# Microcontroller.net
KiCad netlist of a schematic drawn in Altium Designer
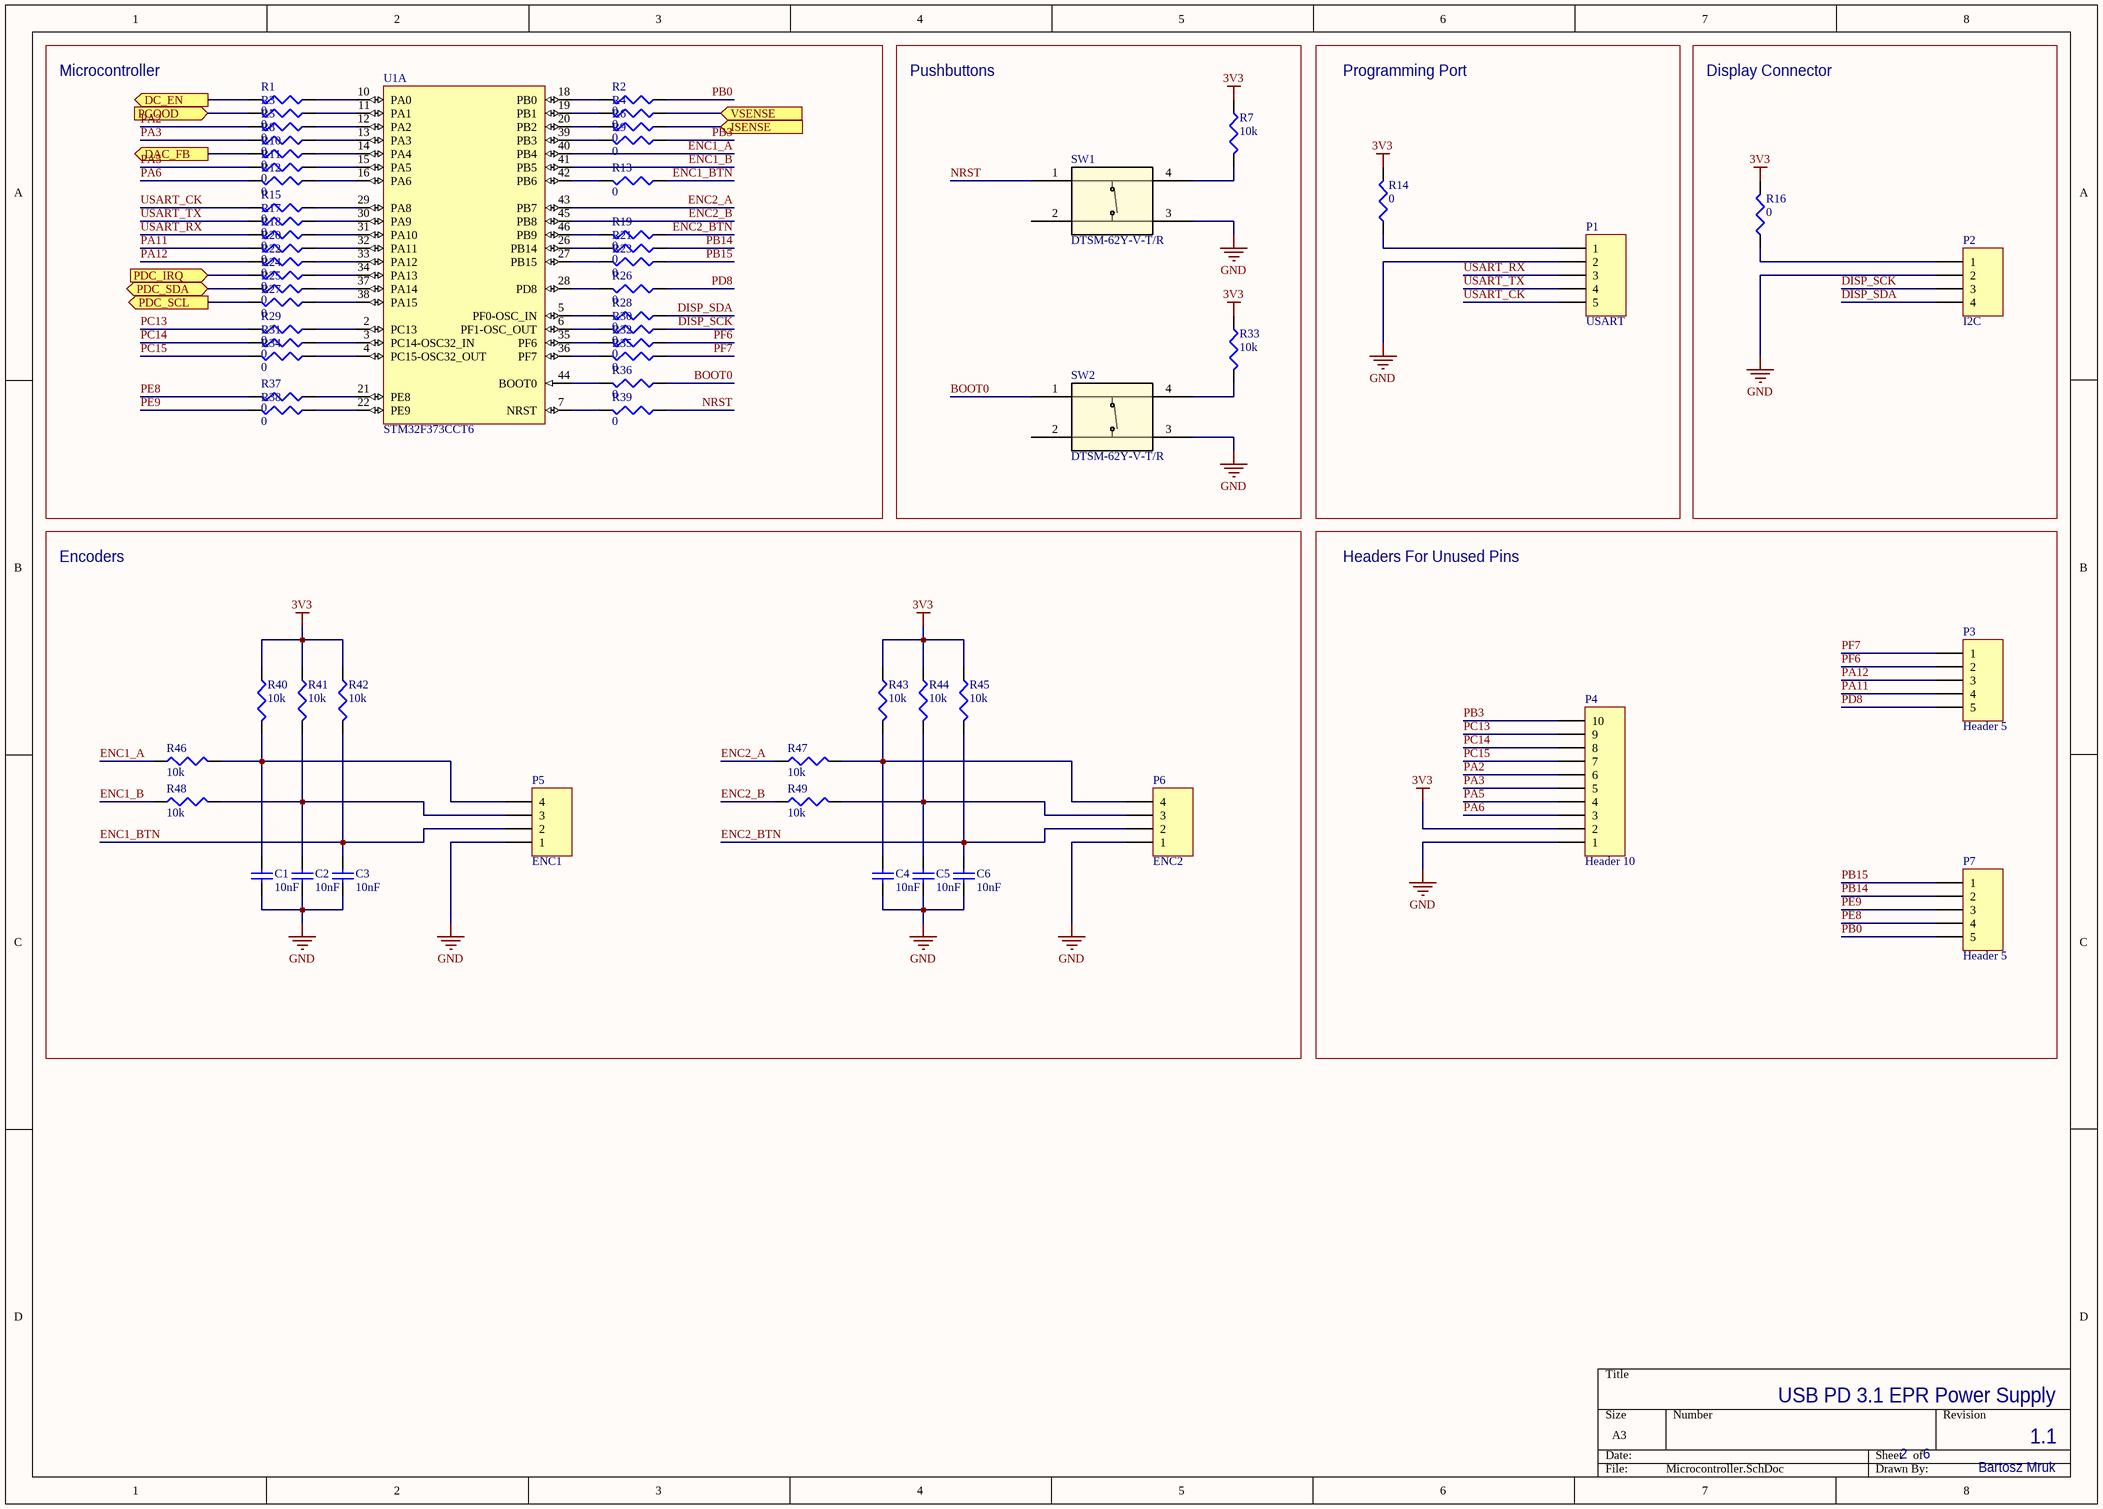
[diagram p0: Microcontroller.SchDoc]

(export (version "E")
  (design (tool "Eeschema 10.0.6"))
  (components
    (comp (ref "C1")
      (value "10nF")
      (footprint "1608[0603]")
      (description "Capacitor (Semiconductor SIM Model)")
      (fields (field (name "Comment") "Cap Semi") (field (name "PUBLISHER") "Altium Limited"))
      (libsource (lib "Miscellaneous Devices") (part "Cap Semi"))
    )
    (comp (ref "C2")
      (value "10nF")
      (footprint "1608[0603]")
      (description "Capacitor (Semiconductor SIM Model)")
      (fields (field (name "Comment") "Cap Semi") (field (name "PUBLISHER") "Altium Limited"))
      (libsource (lib "Miscellaneous Devices") (part "Cap Semi"))
    )
    (comp (ref "C3")
      (value "10nF")
      (footprint "1608[0603]")
      (description "Capacitor (Semiconductor SIM Model)")
      (fields (field (name "Comment") "Cap Semi") (field (name "PUBLISHER") "Altium Limited"))
      (libsource (lib "Miscellaneous Devices") (part "Cap Semi"))
    )
    (comp (ref "C4")
      (value "10nF")
      (footprint "1608[0603]")
      (description "Capacitor (Semiconductor SIM Model)")
      (fields (field (name "Comment") "Cap Semi") (field (name "PUBLISHER") "Altium Limited"))
      (libsource (lib "Miscellaneous Devices") (part "Cap Semi"))
    )
    (comp (ref "C5")
      (value "10nF")
      (footprint "1608[0603]")
      (description "Capacitor (Semiconductor SIM Model)")
      (fields (field (name "Comment") "Cap Semi") (field (name "PUBLISHER") "Altium Limited"))
      (libsource (lib "Miscellaneous Devices") (part "Cap Semi"))
    )
    (comp (ref "C6")
      (value "10nF")
      (footprint "1608[0603]")
      (description "Capacitor (Semiconductor SIM Model)")
      (fields (field (name "Comment") "Cap Semi") (field (name "PUBLISHER") "Altium Limited"))
      (libsource (lib "Miscellaneous Devices") (part "Cap Semi"))
    )
    (comp (ref "P1")
      (value "USART")
      (footprint "HDR1X5")
      (description "Header, 5-Pin")
      (fields (field (name "PUBLISHER") "Altium Limited"))
      (libsource (lib "Miscellaneous Connectors") (part "Header 5"))
    )
    (comp (ref "P2")
      (value "I2C")
      (footprint "HDR1X4")
      (description "Header, 4-Pin")
      (fields (field (name "PUBLISHER") "Altium Limited"))
      (libsource (lib "") (part "Header 4_1"))
    )
    (comp (ref "P3")
      (value "Header 5")
      (footprint "HDR1X5")
      (description "Header, 5-Pin")
      (fields (field (name "PUBLISHER") "Altium Limited"))
      (libsource (lib "Miscellaneous Connectors") (part "Header 5"))
    )
    (comp (ref "P4")
      (value "Header 10")
      (footprint "HDR1X10")
      (description "Header, 10-Pin")
      (fields (field (name "PUBLISHER") "Altium Limited"))
      (libsource (lib "Miscellaneous Connectors") (part "Header 10"))
    )
    (comp (ref "P5")
      (value "ENC1")
      (footprint "HDR1X4")
      (description "Header, 4-Pin")
      (fields (field (name "PUBLISHER") "Altium Limited"))
      (libsource (lib "Miscellaneous Connectors") (part "Header 4"))
    )
    (comp (ref "P6")
      (value "ENC2")
      (footprint "HDR1X4")
      (description "Header, 4-Pin")
      (fields (field (name "PUBLISHER") "Altium Limited"))
      (libsource (lib "Miscellaneous Connectors") (part "Header 4"))
    )
    (comp (ref "P7")
      (value "Header 5")
      (footprint "HDR1X5")
      (description "Header, 5-Pin")
      (fields (field (name "PUBLISHER") "Altium Limited"))
      (libsource (lib "Miscellaneous Connectors") (part "Header 5"))
    )
    (comp (ref "R1")
      (value "0")
      (footprint "J1-0603")
      (description "Resistor")
      (fields (field (name "PUBLISHER") "Altium Limited"))
      (libsource (lib "Miscellaneous Devices") (part "Res3"))
    )
    (comp (ref "R2")
      (value "0")
      (footprint "J1-0603")
      (description "Resistor")
      (fields (field (name "PUBLISHER") "Altium Limited"))
      (libsource (lib "Miscellaneous Devices") (part "Res3"))
    )
    (comp (ref "R3")
      (value "0")
      (footprint "J1-0603")
      (description "Resistor")
      (fields (field (name "PUBLISHER") "Altium Limited"))
      (libsource (lib "Miscellaneous Devices") (part "Res3"))
    )
    (comp (ref "R4")
      (value "0")
      (footprint "J1-0603")
      (description "Resistor")
      (fields (field (name "PUBLISHER") "Altium Limited"))
      (libsource (lib "Miscellaneous Devices") (part "Res3"))
    )
    (comp (ref "R5")
      (value "0")
      (footprint "J1-0603")
      (description "Resistor")
      (fields (field (name "PUBLISHER") "Altium Limited"))
      (libsource (lib "Miscellaneous Devices") (part "Res3"))
    )
    (comp (ref "R6")
      (value "0")
      (footprint "J1-0603")
      (description "Resistor")
      (fields (field (name "PUBLISHER") "Altium Limited"))
      (libsource (lib "Miscellaneous Devices") (part "Res3"))
    )
    (comp (ref "R7")
      (value "10k")
      (footprint "J1-0603")
      (description "Resistor")
      (fields (field (name "PUBLISHER") "Altium Limited"))
      (libsource (lib "Miscellaneous Devices") (part "Res3"))
    )
    (comp (ref "R8")
      (value "0")
      (footprint "J1-0603")
      (description "Resistor")
      (fields (field (name "PUBLISHER") "Altium Limited"))
      (libsource (lib "Miscellaneous Devices") (part "Res3"))
    )
    (comp (ref "R9")
      (value "0")
      (footprint "J1-0603")
      (description "Resistor")
      (fields (field (name "PUBLISHER") "Altium Limited"))
      (libsource (lib "Miscellaneous Devices") (part "Res3"))
    )
    (comp (ref "R10")
      (value "0")
      (footprint "J1-0603")
      (description "Resistor")
      (fields (field (name "PUBLISHER") "Altium Limited"))
      (libsource (lib "Miscellaneous Devices") (part "Res3"))
    )
    (comp (ref "R11")
      (value "0")
      (footprint "J1-0603")
      (description "Resistor")
      (fields (field (name "PUBLISHER") "Altium Limited"))
      (libsource (lib "Miscellaneous Devices") (part "Res3"))
    )
    (comp (ref "R12")
      (value "0")
      (footprint "J1-0603")
      (description "Resistor")
      (fields (field (name "PUBLISHER") "Altium Limited"))
      (libsource (lib "Miscellaneous Devices") (part "Res3"))
    )
    (comp (ref "R13")
      (value "0")
      (footprint "J1-0603")
      (description "Resistor")
      (fields (field (name "PUBLISHER") "Altium Limited"))
      (libsource (lib "Miscellaneous Devices") (part "Res3"))
    )
    (comp (ref "R14")
      (value "0")
      (footprint "J1-0603")
      (description "Resistor")
      (fields (field (name "Comment") "Res3") (field (name "PUBLISHER") "Altium Limited"))
      (libsource (lib "Miscellaneous Devices") (part "Res3"))
    )
    (comp (ref "R15")
      (value "0")
      (footprint "J1-0603")
      (description "Resistor")
      (fields (field (name "PUBLISHER") "Altium Limited"))
      (libsource (lib "Miscellaneous Devices") (part "Res3"))
    )
    (comp (ref "R16")
      (value "0")
      (footprint "J1-0603")
      (description "Resistor")
      (fields (field (name "Comment") "Res3") (field (name "PUBLISHER") "Altium Limited"))
      (libsource (lib "Miscellaneous Devices") (part "Res3"))
    )
    (comp (ref "R17")
      (value "0")
      (footprint "J1-0603")
      (description "Resistor")
      (fields (field (name "PUBLISHER") "Altium Limited"))
      (libsource (lib "Miscellaneous Devices") (part "Res3"))
    )
    (comp (ref "R18")
      (value "0")
      (footprint "J1-0603")
      (description "Resistor")
      (fields (field (name "PUBLISHER") "Altium Limited"))
      (libsource (lib "Miscellaneous Devices") (part "Res3"))
    )
    (comp (ref "R19")
      (value "0")
      (footprint "J1-0603")
      (description "Resistor")
      (fields (field (name "PUBLISHER") "Altium Limited"))
      (libsource (lib "Miscellaneous Devices") (part "Res3"))
    )
    (comp (ref "R20")
      (value "0")
      (footprint "J1-0603")
      (description "Resistor")
      (fields (field (name "PUBLISHER") "Altium Limited"))
      (libsource (lib "Miscellaneous Devices") (part "Res3"))
    )
    (comp (ref "R21")
      (value "0")
      (footprint "J1-0603")
      (description "Resistor")
      (fields (field (name "PUBLISHER") "Altium Limited"))
      (libsource (lib "Miscellaneous Devices") (part "Res3"))
    )
    (comp (ref "R22")
      (value "0")
      (footprint "J1-0603")
      (description "Resistor")
      (fields (field (name "PUBLISHER") "Altium Limited"))
      (libsource (lib "Miscellaneous Devices") (part "Res3"))
    )
    (comp (ref "R23")
      (value "0")
      (footprint "J1-0603")
      (description "Resistor")
      (fields (field (name "PUBLISHER") "Altium Limited"))
      (libsource (lib "Miscellaneous Devices") (part "Res3"))
    )
    (comp (ref "R24")
      (value "0")
      (footprint "J1-0603")
      (description "Resistor")
      (fields (field (name "PUBLISHER") "Altium Limited"))
      (libsource (lib "Miscellaneous Devices") (part "Res3"))
    )
    (comp (ref "R25")
      (value "0")
      (footprint "J1-0603")
      (description "Resistor")
      (fields (field (name "PUBLISHER") "Altium Limited"))
      (libsource (lib "Miscellaneous Devices") (part "Res3"))
    )
    (comp (ref "R26")
      (value "0")
      (footprint "J1-0603")
      (description "Resistor")
      (fields (field (name "PUBLISHER") "Altium Limited"))
      (libsource (lib "Miscellaneous Devices") (part "Res3"))
    )
    (comp (ref "R27")
      (value "0")
      (footprint "J1-0603")
      (description "Resistor")
      (fields (field (name "PUBLISHER") "Altium Limited"))
      (libsource (lib "Miscellaneous Devices") (part "Res3"))
    )
    (comp (ref "R28")
      (value "0")
      (footprint "J1-0603")
      (description "Resistor")
      (fields (field (name "PUBLISHER") "Altium Limited"))
      (libsource (lib "Miscellaneous Devices") (part "Res3"))
    )
    (comp (ref "R29")
      (value "0")
      (footprint "J1-0603")
      (description "Resistor")
      (fields (field (name "PUBLISHER") "Altium Limited"))
      (libsource (lib "Miscellaneous Devices") (part "Res3"))
    )
    (comp (ref "R30")
      (value "0")
      (footprint "J1-0603")
      (description "Resistor")
      (fields (field (name "PUBLISHER") "Altium Limited"))
      (libsource (lib "Miscellaneous Devices") (part "Res3"))
    )
    (comp (ref "R31")
      (value "0")
      (footprint "J1-0603")
      (description "Resistor")
      (fields (field (name "PUBLISHER") "Altium Limited"))
      (libsource (lib "Miscellaneous Devices") (part "Res3"))
    )
    (comp (ref "R32")
      (value "0")
      (footprint "J1-0603")
      (description "Resistor")
      (fields (field (name "PUBLISHER") "Altium Limited"))
      (libsource (lib "Miscellaneous Devices") (part "Res3"))
    )
    (comp (ref "R33")
      (value "10k")
      (footprint "J1-0603")
      (description "Resistor")
      (fields (field (name "PUBLISHER") "Altium Limited"))
      (libsource (lib "Miscellaneous Devices") (part "Res3"))
    )
    (comp (ref "R34")
      (value "0")
      (footprint "J1-0603")
      (description "Resistor")
      (fields (field (name "PUBLISHER") "Altium Limited"))
      (libsource (lib "Miscellaneous Devices") (part "Res3"))
    )
    (comp (ref "R35")
      (value "0")
      (footprint "J1-0603")
      (description "Resistor")
      (fields (field (name "PUBLISHER") "Altium Limited"))
      (libsource (lib "Miscellaneous Devices") (part "Res3"))
    )
    (comp (ref "R36")
      (value "0")
      (footprint "J1-0603")
      (description "Resistor")
      (fields (field (name "PUBLISHER") "Altium Limited"))
      (libsource (lib "Miscellaneous Devices") (part "Res3"))
    )
    (comp (ref "R37")
      (value "0")
      (footprint "J1-0603")
      (description "Resistor")
      (fields (field (name "PUBLISHER") "Altium Limited"))
      (libsource (lib "Miscellaneous Devices") (part "Res3"))
    )
    (comp (ref "R38")
      (value "0")
      (footprint "J1-0603")
      (description "Resistor")
      (fields (field (name "PUBLISHER") "Altium Limited"))
      (libsource (lib "Miscellaneous Devices") (part "Res3"))
    )
    (comp (ref "R39")
      (value "0")
      (footprint "J1-0603")
      (description "Resistor")
      (fields (field (name "PUBLISHER") "Altium Limited"))
      (libsource (lib "Miscellaneous Devices") (part "Res3"))
    )
    (comp (ref "R40")
      (value "10k")
      (footprint "J1-0603")
      (description "Resistor")
      (fields (field (name "PUBLISHER") "Altium Limited"))
      (libsource (lib "Miscellaneous Devices") (part "Res3"))
    )
    (comp (ref "R41")
      (value "10k")
      (footprint "J1-0603")
      (description "Resistor")
      (fields (field (name "PUBLISHER") "Altium Limited"))
      (libsource (lib "Miscellaneous Devices") (part "Res3"))
    )
    (comp (ref "R42")
      (value "10k")
      (footprint "J1-0603")
      (description "Resistor")
      (fields (field (name "PUBLISHER") "Altium Limited"))
      (libsource (lib "Miscellaneous Devices") (part "Res3"))
    )
    (comp (ref "R43")
      (value "10k")
      (footprint "J1-0603")
      (description "Resistor")
      (fields (field (name "PUBLISHER") "Altium Limited"))
      (libsource (lib "Miscellaneous Devices") (part "Res3"))
    )
    (comp (ref "R44")
      (value "10k")
      (footprint "J1-0603")
      (description "Resistor")
      (fields (field (name "PUBLISHER") "Altium Limited"))
      (libsource (lib "Miscellaneous Devices") (part "Res3"))
    )
    (comp (ref "R45")
      (value "10k")
      (footprint "J1-0603")
      (description "Resistor")
      (fields (field (name "PUBLISHER") "Altium Limited"))
      (libsource (lib "Miscellaneous Devices") (part "Res3"))
    )
    (comp (ref "R46")
      (value "10k")
      (footprint "J1-0603")
      (description "Resistor")
      (fields (field (name "PUBLISHER") "Altium Limited"))
      (libsource (lib "Miscellaneous Devices") (part "Res3"))
    )
    (comp (ref "R47")
      (value "10k")
      (footprint "J1-0603")
      (description "Resistor")
      (fields (field (name "PUBLISHER") "Altium Limited"))
      (libsource (lib "Miscellaneous Devices") (part "Res3"))
    )
    (comp (ref "R48")
      (value "10k")
      (footprint "J1-0603")
      (description "Resistor")
      (fields (field (name "PUBLISHER") "Altium Limited"))
      (libsource (lib "Miscellaneous Devices") (part "Res3"))
    )
    (comp (ref "R49")
      (value "10k")
      (footprint "J1-0603")
      (description "Resistor")
      (fields (field (name "PUBLISHER") "Altium Limited"))
      (libsource (lib "Miscellaneous Devices") (part "Res3"))
    )
    (comp (ref "SW1")
      (value "DTSM-62Y-V-T/R")
      (footprint "DTSM-62_DIP")
      (description "Description")
      (fields (field (name "COPYRIGHT") "Copyright (C) 2025 Ultra Librarian. All rights reserved."))
      (libsource (lib "DTSM-62Y-V-TR") (part "DTSM-62Y-V-TR"))
    )
    (comp (ref "SW2")
      (value "DTSM-62Y-V-T/R")
      (footprint "DTSM-62_DIP")
      (description "Description")
      (fields (field (name "COPYRIGHT") "Copyright (C) 2025 Ultra Librarian. All rights reserved."))
      (libsource (lib "DTSM-62Y-V-TR") (part "DTSM-62Y-V-TR"))
    )
    (comp (ref "U1")
      (value "STM32F373CCT6")
      (footprint "STM-LQFP48_M")
      (libsource (lib "Altium Content Vault") (part "MC-ARM-STM32F373-SQ48"))
    )
  )
  (nets
    (net (code "1") (name "/BOOT0") (class "Default")
      (node (ref "R36") (pin "1") (pinfunction "1_1") (pintype "passive"))
      (node (ref "SW2") (pin "1") (pinfunction "1_1") (pintype "passive"))
    )
    (net (code "2") (name "/DAC_FB") (class "Default")
      (node (ref "R10") (pin "2") (pinfunction "2_2") (pintype "passive"))
    )
    (net (code "3") (name "/DC_EN") (class "Default")
      (node (ref "R1") (pin "2") (pinfunction "2_2") (pintype "passive"))
    )
    (net (code "4") (name "/DISP_SCK") (class "Default")
      (node (ref "P2") (pin "3") (pinfunction "3_3") (pintype "passive"))
      (node (ref "R30") (pin "1") (pinfunction "1_1") (pintype "passive"))
    )
    (net (code "5") (name "/DISP_SDA") (class "Default")
      (node (ref "P2") (pin "4") (pinfunction "4_4") (pintype "passive"))
      (node (ref "R28") (pin "1") (pinfunction "1_1") (pintype "passive"))
    )
    (net (code "6") (name "/ENC1_A") (class "Default")
      (node (ref "R46") (pin "1") (pinfunction "1_1") (pintype "passive"))
      (node (ref "U1") (pin "40") (pinfunction "PB4_40") (pintype "bidirectional"))
    )
    (net (code "7") (name "/ENC1_B") (class "Default")
      (node (ref "R48") (pin "1") (pinfunction "1_1") (pintype "passive"))
      (node (ref "U1") (pin "41") (pinfunction "PB5_41") (pintype "bidirectional"))
    )
    (net (code "8") (name "/ENC1_BTN") (class "Default")
      (node (ref "C3") (pin "2") (pinfunction "2_2") (pintype "passive"))
      (node (ref "P5") (pin "2") (pinfunction "2_2") (pintype "passive"))
      (node (ref "R13") (pin "1") (pinfunction "1_1") (pintype "passive"))
      (node (ref "R42") (pin "2") (pinfunction "2_2") (pintype "passive"))
    )
    (net (code "9") (name "/ENC2_A") (class "Default")
      (node (ref "R47") (pin "1") (pinfunction "1_1") (pintype "passive"))
      (node (ref "U1") (pin "43") (pinfunction "PB7_43") (pintype "bidirectional"))
    )
    (net (code "10") (name "/ENC2_B") (class "Default")
      (node (ref "R49") (pin "1") (pinfunction "1_1") (pintype "passive"))
      (node (ref "U1") (pin "45") (pinfunction "PB8_45") (pintype "bidirectional"))
    )
    (net (code "11") (name "/ENC2_BTN") (class "Default")
      (node (ref "C6") (pin "2") (pinfunction "2_2") (pintype "passive"))
      (node (ref "P6") (pin "2") (pinfunction "2_2") (pintype "passive"))
      (node (ref "R19") (pin "1") (pinfunction "1_1") (pintype "passive"))
      (node (ref "R45") (pin "2") (pinfunction "2_2") (pintype "passive"))
    )
    (net (code "12") (name "/ISENSE") (class "Default")
      (node (ref "R6") (pin "1") (pinfunction "1_1") (pintype "passive"))
    )
    (net (code "13") (name "/NRST") (class "Default")
      (node (ref "R39") (pin "1") (pinfunction "1_1") (pintype "passive"))
      (node (ref "SW1") (pin "1") (pinfunction "1_1") (pintype "passive"))
    )
    (net (code "14") (name "/PA2") (class "Default")
      (node (ref "P4") (pin "6") (pinfunction "6_6") (pintype "passive"))
      (node (ref "R5") (pin "2") (pinfunction "2_2") (pintype "passive"))
    )
    (net (code "15") (name "/PA3") (class "Default")
      (node (ref "P4") (pin "5") (pinfunction "5_5") (pintype "passive"))
      (node (ref "R8") (pin "2") (pinfunction "2_2") (pintype "passive"))
    )
    (net (code "16") (name "/PA5") (class "Default")
      (node (ref "P4") (pin "4") (pinfunction "4_4") (pintype "passive"))
      (node (ref "R11") (pin "2") (pinfunction "2_2") (pintype "passive"))
    )
    (net (code "17") (name "/PA6") (class "Default")
      (node (ref "P4") (pin "3") (pinfunction "3_3") (pintype "passive"))
      (node (ref "R12") (pin "2") (pinfunction "2_2") (pintype "passive"))
    )
    (net (code "18") (name "/PA11") (class "Default")
      (node (ref "P3") (pin "4") (pinfunction "4_4") (pintype "passive"))
      (node (ref "R20") (pin "2") (pinfunction "2_2") (pintype "passive"))
    )
    (net (code "19") (name "/PA12") (class "Default")
      (node (ref "P3") (pin "3") (pinfunction "3_3") (pintype "passive"))
      (node (ref "R22") (pin "2") (pinfunction "2_2") (pintype "passive"))
    )
    (net (code "20") (name "/PB0") (class "Default")
      (node (ref "P7") (pin "5") (pinfunction "5_5") (pintype "passive"))
      (node (ref "R2") (pin "1") (pinfunction "1_1") (pintype "passive"))
    )
    (net (code "21") (name "/PB3") (class "Default")
      (node (ref "P4") (pin "10") (pinfunction "10_10") (pintype "passive"))
      (node (ref "R9") (pin "1") (pinfunction "1_1") (pintype "passive"))
    )
    (net (code "22") (name "/PB14") (class "Default")
      (node (ref "P7") (pin "2") (pinfunction "2_2") (pintype "passive"))
      (node (ref "R21") (pin "1") (pinfunction "1_1") (pintype "passive"))
    )
    (net (code "23") (name "/PB15") (class "Default")
      (node (ref "P7") (pin "1") (pinfunction "1_1") (pintype "passive"))
      (node (ref "R23") (pin "1") (pinfunction "1_1") (pintype "passive"))
    )
    (net (code "24") (name "/PC13") (class "Default")
      (node (ref "P4") (pin "9") (pinfunction "9_9") (pintype "passive"))
      (node (ref "R29") (pin "2") (pinfunction "2_2") (pintype "passive"))
    )
    (net (code "25") (name "/PC14") (class "Default")
      (node (ref "P4") (pin "8") (pinfunction "8_8") (pintype "passive"))
      (node (ref "R31") (pin "2") (pinfunction "2_2") (pintype "passive"))
    )
    (net (code "26") (name "/PC15") (class "Default")
      (node (ref "P4") (pin "7") (pinfunction "7_7") (pintype "passive"))
      (node (ref "R34") (pin "2") (pinfunction "2_2") (pintype "passive"))
    )
    (net (code "27") (name "/PD8") (class "Default")
      (node (ref "P3") (pin "5") (pinfunction "5_5") (pintype "passive"))
      (node (ref "R26") (pin "1") (pinfunction "1_1") (pintype "passive"))
    )
    (net (code "28") (name "/PDC_IRQ") (class "Default")
      (node (ref "R24") (pin "2") (pinfunction "2_2") (pintype "passive"))
    )
    (net (code "29") (name "/PDC_SCL") (class "Default")
      (node (ref "R27") (pin "2") (pinfunction "2_2") (pintype "passive"))
    )
    (net (code "30") (name "/PDC_SDA") (class "Default")
      (node (ref "R25") (pin "2") (pinfunction "2_2") (pintype "passive"))
    )
    (net (code "31") (name "/PE8") (class "Default")
      (node (ref "P7") (pin "4") (pinfunction "4_4") (pintype "passive"))
      (node (ref "R37") (pin "2") (pinfunction "2_2") (pintype "passive"))
    )
    (net (code "32") (name "/PE9") (class "Default")
      (node (ref "P7") (pin "3") (pinfunction "3_3") (pintype "passive"))
      (node (ref "R38") (pin "2") (pinfunction "2_2") (pintype "passive"))
    )
    (net (code "33") (name "/PF6") (class "Default")
      (node (ref "P3") (pin "2") (pinfunction "2_2") (pintype "passive"))
      (node (ref "R32") (pin "1") (pinfunction "1_1") (pintype "passive"))
    )
    (net (code "34") (name "/PF7") (class "Default")
      (node (ref "P3") (pin "1") (pinfunction "1_1") (pintype "passive"))
      (node (ref "R35") (pin "1") (pinfunction "1_1") (pintype "passive"))
    )
    (net (code "35") (name "/PGOOD") (class "Default")
      (node (ref "R3") (pin "2") (pinfunction "2_2") (pintype "passive"))
    )
    (net (code "36") (name "/USART_CK") (class "Default")
      (node (ref "P1") (pin "5") (pinfunction "5_5") (pintype "passive"))
      (node (ref "R15") (pin "2") (pinfunction "2_2") (pintype "passive"))
    )
    (net (code "37") (name "/USART_RX") (class "Default")
      (node (ref "P1") (pin "3") (pinfunction "3_3") (pintype "passive"))
      (node (ref "R18") (pin "2") (pinfunction "2_2") (pintype "passive"))
    )
    (net (code "38") (name "/USART_TX") (class "Default")
      (node (ref "P1") (pin "4") (pinfunction "4_4") (pintype "passive"))
      (node (ref "R17") (pin "2") (pinfunction "2_2") (pintype "passive"))
    )
    (net (code "39") (name "/VSENSE") (class "Default")
      (node (ref "R4") (pin "1") (pinfunction "1_1") (pintype "passive"))
    )
    (net (code "40") (name "3V3") (class "Default")
      (node (ref "P4") (pin "2") (pinfunction "2_2") (pintype "passive"))
      (node (ref "R14") (pin "2") (pinfunction "2_2") (pintype "passive"))
      (node (ref "R16") (pin "2") (pinfunction "2_2") (pintype "passive"))
      (node (ref "R33") (pin "1") (pinfunction "1_1") (pintype "passive"))
      (node (ref "R40") (pin "1") (pinfunction "1_1") (pintype "passive"))
      (node (ref "R41") (pin "1") (pinfunction "1_1") (pintype "passive"))
      (node (ref "R42") (pin "1") (pinfunction "1_1") (pintype "passive"))
      (node (ref "R43") (pin "1") (pinfunction "1_1") (pintype "passive"))
      (node (ref "R44") (pin "1") (pinfunction "1_1") (pintype "passive"))
      (node (ref "R45") (pin "1") (pinfunction "1_1") (pintype "passive"))
      (node (ref "R7") (pin "1") (pinfunction "1_1") (pintype "passive"))
    )
    (net (code "41") (name "GND") (class "Default")
      (node (ref "C1") (pin "1") (pinfunction "1_1") (pintype "passive"))
      (node (ref "C2") (pin "1") (pinfunction "1_1") (pintype "passive"))
      (node (ref "C3") (pin "1") (pinfunction "1_1") (pintype "passive"))
      (node (ref "C4") (pin "1") (pinfunction "1_1") (pintype "passive"))
      (node (ref "C5") (pin "1") (pinfunction "1_1") (pintype "passive"))
      (node (ref "C6") (pin "1") (pinfunction "1_1") (pintype "passive"))
      (node (ref "P1") (pin "2") (pinfunction "2_2") (pintype "passive"))
      (node (ref "P2") (pin "2") (pinfunction "2_2") (pintype "passive"))
      (node (ref "P4") (pin "1") (pinfunction "1_1") (pintype "passive"))
      (node (ref "P5") (pin "1") (pinfunction "1_1") (pintype "passive"))
      (node (ref "P6") (pin "1") (pinfunction "1_1") (pintype "passive"))
      (node (ref "SW1") (pin "3") (pinfunction "3_3") (pintype "passive"))
      (node (ref "SW2") (pin "3") (pinfunction "3_3") (pintype "passive"))
    )
    (net (code "42") (name "Net-(C1-Pad2)") (class "Default")
      (node (ref "C1") (pin "2") (pinfunction "2_2") (pintype "passive"))
      (node (ref "P5") (pin "4") (pinfunction "4_4") (pintype "passive"))
      (node (ref "R40") (pin "2") (pinfunction "2_2") (pintype "passive"))
      (node (ref "R46") (pin "2") (pinfunction "2_2") (pintype "passive"))
    )
    (net (code "43") (name "Net-(C2-Pad2)") (class "Default")
      (node (ref "C2") (pin "2") (pinfunction "2_2") (pintype "passive"))
      (node (ref "P5") (pin "3") (pinfunction "3_3") (pintype "passive"))
      (node (ref "R41") (pin "2") (pinfunction "2_2") (pintype "passive"))
      (node (ref "R48") (pin "2") (pinfunction "2_2") (pintype "passive"))
    )
    (net (code "44") (name "Net-(C4-Pad2)") (class "Default")
      (node (ref "C4") (pin "2") (pinfunction "2_2") (pintype "passive"))
      (node (ref "P6") (pin "4") (pinfunction "4_4") (pintype "passive"))
      (node (ref "R43") (pin "2") (pinfunction "2_2") (pintype "passive"))
      (node (ref "R47") (pin "2") (pinfunction "2_2") (pintype "passive"))
    )
    (net (code "45") (name "Net-(C5-Pad2)") (class "Default")
      (node (ref "C5") (pin "2") (pinfunction "2_2") (pintype "passive"))
      (node (ref "P6") (pin "3") (pinfunction "3_3") (pintype "passive"))
      (node (ref "R44") (pin "2") (pinfunction "2_2") (pintype "passive"))
      (node (ref "R49") (pin "2") (pinfunction "2_2") (pintype "passive"))
    )
    (net (code "46") (name "Net-(P1-Pad1)") (class "Default")
      (node (ref "P1") (pin "1") (pinfunction "1_1") (pintype "passive"))
      (node (ref "R14") (pin "1") (pinfunction "1_1") (pintype "passive"))
    )
    (net (code "47") (name "Net-(P2-Pad1)") (class "Default")
      (node (ref "P2") (pin "1") (pinfunction "1_1") (pintype "passive"))
      (node (ref "R16") (pin "1") (pinfunction "1_1") (pintype "passive"))
    )
    (net (code "48") (name "Net-(R7-Pad2)") (class "Default")
      (node (ref "R7") (pin "2") (pinfunction "2_2") (pintype "passive"))
      (node (ref "SW1") (pin "4") (pinfunction "4_4") (pintype "passive"))
    )
    (net (code "49") (name "Net-(R33-Pad2)") (class "Default")
      (node (ref "R33") (pin "2") (pinfunction "2_2") (pintype "passive"))
      (node (ref "SW2") (pin "4") (pinfunction "4_4") (pintype "passive"))
    )
    (net (code "50") (name "Net-(U1A-BOOT0)") (class "Default")
      (node (ref "R36") (pin "2") (pinfunction "2_2") (pintype "passive"))
      (node (ref "U1") (pin "44") (pinfunction "BOOT0_44") (pintype "input"))
    )
    (net (code "51") (name "Net-(U1A-NRST)") (class "Default")
      (node (ref "R39") (pin "2") (pinfunction "2_2") (pintype "passive"))
      (node (ref "U1") (pin "7") (pinfunction "NRST_7") (pintype "bidirectional"))
    )
    (net (code "52") (name "Net-(U1A-PA0)") (class "Default")
      (node (ref "R1") (pin "1") (pinfunction "1_1") (pintype "passive"))
      (node (ref "U1") (pin "10") (pinfunction "PA0_10") (pintype "bidirectional"))
    )
    (net (code "53") (name "Net-(U1A-PA1)") (class "Default")
      (node (ref "R3") (pin "1") (pinfunction "1_1") (pintype "passive"))
      (node (ref "U1") (pin "11") (pinfunction "PA1_11") (pintype "bidirectional"))
    )
    (net (code "54") (name "Net-(U1A-PA2)") (class "Default")
      (node (ref "R5") (pin "1") (pinfunction "1_1") (pintype "passive"))
      (node (ref "U1") (pin "12") (pinfunction "PA2_12") (pintype "bidirectional"))
    )
    (net (code "55") (name "Net-(U1A-PA3)") (class "Default")
      (node (ref "R8") (pin "1") (pinfunction "1_1") (pintype "passive"))
      (node (ref "U1") (pin "13") (pinfunction "PA3_13") (pintype "bidirectional"))
    )
    (net (code "56") (name "Net-(U1A-PA4)") (class "Default")
      (node (ref "R10") (pin "1") (pinfunction "1_1") (pintype "passive"))
      (node (ref "U1") (pin "14") (pinfunction "PA4_14") (pintype "bidirectional"))
    )
    (net (code "57") (name "Net-(U1A-PA5)") (class "Default")
      (node (ref "R11") (pin "1") (pinfunction "1_1") (pintype "passive"))
      (node (ref "U1") (pin "15") (pinfunction "PA5_15") (pintype "bidirectional"))
    )
    (net (code "58") (name "Net-(U1A-PA6)") (class "Default")
      (node (ref "R12") (pin "1") (pinfunction "1_1") (pintype "passive"))
      (node (ref "U1") (pin "16") (pinfunction "PA6_16") (pintype "bidirectional"))
    )
    (net (code "59") (name "Net-(U1A-PA8)") (class "Default")
      (node (ref "R15") (pin "1") (pinfunction "1_1") (pintype "passive"))
      (node (ref "U1") (pin "29") (pinfunction "PA8_29") (pintype "bidirectional"))
    )
    (net (code "60") (name "Net-(U1A-PA9)") (class "Default")
      (node (ref "R17") (pin "1") (pinfunction "1_1") (pintype "passive"))
      (node (ref "U1") (pin "30") (pinfunction "PA9_30") (pintype "bidirectional"))
    )
    (net (code "61") (name "Net-(U1A-PA10)") (class "Default")
      (node (ref "R18") (pin "1") (pinfunction "1_1") (pintype "passive"))
      (node (ref "U1") (pin "31") (pinfunction "PA10_31") (pintype "bidirectional"))
    )
    (net (code "62") (name "Net-(U1A-PA11)") (class "Default")
      (node (ref "R20") (pin "1") (pinfunction "1_1") (pintype "passive"))
      (node (ref "U1") (pin "32") (pinfunction "PA11_32") (pintype "bidirectional"))
    )
    (net (code "63") (name "Net-(U1A-PA12)") (class "Default")
      (node (ref "R22") (pin "1") (pinfunction "1_1") (pintype "passive"))
      (node (ref "U1") (pin "33") (pinfunction "PA12_33") (pintype "bidirectional"))
    )
    (net (code "64") (name "Net-(U1A-PA13)") (class "Default")
      (node (ref "R24") (pin "1") (pinfunction "1_1") (pintype "passive"))
      (node (ref "U1") (pin "34") (pinfunction "PA13_34") (pintype "bidirectional"))
    )
    (net (code "65") (name "Net-(U1A-PA14)") (class "Default")
      (node (ref "R25") (pin "1") (pinfunction "1_1") (pintype "passive"))
      (node (ref "U1") (pin "37") (pinfunction "PA14_37") (pintype "bidirectional"))
    )
    (net (code "66") (name "Net-(U1A-PA15)") (class "Default")
      (node (ref "R27") (pin "1") (pinfunction "1_1") (pintype "passive"))
      (node (ref "U1") (pin "38") (pinfunction "PA15_38") (pintype "bidirectional"))
    )
    (net (code "67") (name "Net-(U1A-PB0)") (class "Default")
      (node (ref "R2") (pin "2") (pinfunction "2_2") (pintype "passive"))
      (node (ref "U1") (pin "18") (pinfunction "PB0_18") (pintype "bidirectional"))
    )
    (net (code "68") (name "Net-(U1A-PB1)") (class "Default")
      (node (ref "R4") (pin "2") (pinfunction "2_2") (pintype "passive"))
      (node (ref "U1") (pin "19") (pinfunction "PB1_19") (pintype "bidirectional"))
    )
    (net (code "69") (name "Net-(U1A-PB2)") (class "Default")
      (node (ref "R6") (pin "2") (pinfunction "2_2") (pintype "passive"))
      (node (ref "U1") (pin "20") (pinfunction "PB2_20") (pintype "bidirectional"))
    )
    (net (code "70") (name "Net-(U1A-PB3)") (class "Default")
      (node (ref "R9") (pin "2") (pinfunction "2_2") (pintype "passive"))
      (node (ref "U1") (pin "39") (pinfunction "PB3_39") (pintype "bidirectional"))
    )
    (net (code "71") (name "Net-(U1A-PB6)") (class "Default")
      (node (ref "R13") (pin "2") (pinfunction "2_2") (pintype "passive"))
      (node (ref "U1") (pin "42") (pinfunction "PB6_42") (pintype "bidirectional"))
    )
    (net (code "72") (name "Net-(U1A-PB9)") (class "Default")
      (node (ref "R19") (pin "2") (pinfunction "2_2") (pintype "passive"))
      (node (ref "U1") (pin "46") (pinfunction "PB9_46") (pintype "bidirectional"))
    )
    (net (code "73") (name "Net-(U1A-PB14)") (class "Default")
      (node (ref "R21") (pin "2") (pinfunction "2_2") (pintype "passive"))
      (node (ref "U1") (pin "26") (pinfunction "PB14_26") (pintype "bidirectional"))
    )
    (net (code "74") (name "Net-(U1A-PB15)") (class "Default")
      (node (ref "R23") (pin "2") (pinfunction "2_2") (pintype "passive"))
      (node (ref "U1") (pin "27") (pinfunction "PB15_27") (pintype "bidirectional"))
    )
    (net (code "75") (name "Net-(U1A-PC13)") (class "Default")
      (node (ref "R29") (pin "1") (pinfunction "1_1") (pintype "passive"))
      (node (ref "U1") (pin "2") (pinfunction "PC13_2") (pintype "bidirectional"))
    )
    (net (code "76") (name "Net-(U1A-PC14-OSC32_IN)") (class "Default")
      (node (ref "R31") (pin "1") (pinfunction "1_1") (pintype "passive"))
      (node (ref "U1") (pin "3") (pinfunction "PC14-OSC32_IN_3") (pintype "bidirectional"))
    )
    (net (code "77") (name "Net-(U1A-PC15-OSC32_OUT)") (class "Default")
      (node (ref "R34") (pin "1") (pinfunction "1_1") (pintype "passive"))
      (node (ref "U1") (pin "4") (pinfunction "PC15-OSC32_OUT_4") (pintype "bidirectional"))
    )
    (net (code "78") (name "Net-(U1A-PD8)") (class "Default")
      (node (ref "R26") (pin "2") (pinfunction "2_2") (pintype "passive"))
      (node (ref "U1") (pin "28") (pinfunction "PD8_28") (pintype "bidirectional"))
    )
    (net (code "79") (name "Net-(U1A-PE8)") (class "Default")
      (node (ref "R37") (pin "1") (pinfunction "1_1") (pintype "passive"))
      (node (ref "U1") (pin "21") (pinfunction "PE8_21") (pintype "bidirectional"))
    )
    (net (code "80") (name "Net-(U1A-PE9)") (class "Default")
      (node (ref "R38") (pin "1") (pinfunction "1_1") (pintype "passive"))
      (node (ref "U1") (pin "22") (pinfunction "PE9_22") (pintype "bidirectional"))
    )
    (net (code "81") (name "Net-(U1A-PF0-OSC_IN)") (class "Default")
      (node (ref "R28") (pin "2") (pinfunction "2_2") (pintype "passive"))
      (node (ref "U1") (pin "5") (pinfunction "PF0-OSC_IN_5") (pintype "bidirectional"))
    )
    (net (code "82") (name "Net-(U1A-PF1-OSC_OUT)") (class "Default")
      (node (ref "R30") (pin "2") (pinfunction "2_2") (pintype "passive"))
      (node (ref "U1") (pin "6") (pinfunction "PF1-OSC_OUT_6") (pintype "bidirectional"))
    )
    (net (code "83") (name "Net-(U1A-PF6)") (class "Default")
      (node (ref "R32") (pin "2") (pinfunction "2_2") (pintype "passive"))
      (node (ref "U1") (pin "35") (pinfunction "PF6_35") (pintype "bidirectional"))
    )
    (net (code "84") (name "Net-(U1A-PF7)") (class "Default")
      (node (ref "R35") (pin "2") (pinfunction "2_2") (pintype "passive"))
      (node (ref "U1") (pin "36") (pinfunction "PF7_36") (pintype "bidirectional"))
    )
    (net (code "85") (name "unconnected-(SW1-Pad2)") (class "Default")
      (node (ref "SW1") (pin "2") (pinfunction "2_2") (pintype "passive"))
    )
    (net (code "86") (name "unconnected-(SW2-Pad2)") (class "Default")
      (node (ref "SW2") (pin "2") (pinfunction "2_2") (pintype "passive"))
    )
  )
)
